# Sheet2.net
KiCad netlist of a schematic drawn in Altium Designer
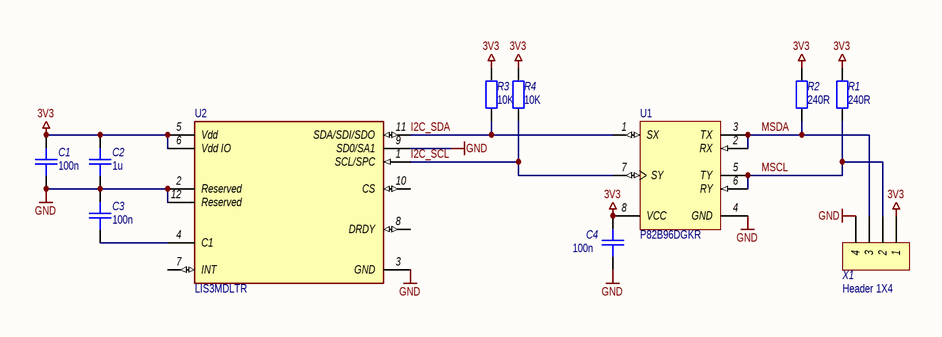
[diagram p0: Sheet2.SchDoc]

(export (version "E")
  (design (tool "Eeschema 10.0.6"))
  (components
    (comp (ref "C1")
      (value "100n")
      (footprint "SMD_C0402")
      (description "Capacitor")
      (fields (field (name "Comment") "K10-79"))
      (libsource (lib "Capacitor") (part "Capacitor"))
    )
    (comp (ref "C2")
      (value "1u")
      (footprint "SMD_C0402")
      (description "Capacitor")
      (fields (field (name "Comment") "K10-79"))
      (libsource (lib "Capacitor") (part "Capacitor"))
    )
    (comp (ref "C3")
      (value "100n")
      (footprint "SMD_C0402")
      (description "Capacitor")
      (fields (field (name "Comment") "K10-79"))
      (libsource (lib "Capacitor") (part "Capacitor"))
    )
    (comp (ref "C4")
      (value "100n")
      (footprint "SMD_C0402")
      (description "Capacitor")
      (fields (field (name "Comment") "K10-79"))
      (libsource (lib "Capacitor") (part "Capacitor"))
    )
    (comp (ref "R1")
      (value "240R")
      (footprint "SMD_0402")
      (description "Resistor")
      (fields (field (name "Comment") "OSM R1-8"))
      (libsource (lib "Resistor") (part "Resistor"))
    )
    (comp (ref "R2")
      (value "240R")
      (footprint "SMD_0402")
      (description "Resistor")
      (fields (field (name "Comment") "OSM R1-8"))
      (libsource (lib "Resistor") (part "Resistor"))
    )
    (comp (ref "R3")
      (value "10K")
      (footprint "SMD_0402")
      (description "Resistor")
      (fields (field (name "Comment") "OSM R1-8"))
      (libsource (lib "") (part "Resistor_1"))
    )
    (comp (ref "R4")
      (value "10K")
      (footprint "SMD_0402")
      (description "Resistor")
      (fields (field (name "Comment") "OSM R1-8"))
      (libsource (lib "Resistor") (part "Resistor"))
    )
    (comp (ref "U1")
      (value "P82B96DGKR")
      (footprint "DGK0008A_M")
      (fields (field (name "MANUFACTURER") "Texas Instruments"))
      (libsource (lib "P82B96DGKR") (part "CMP-0314-00301-2"))
    )
    (comp (ref "U2")
      (value "LIS3MDLTR")
      (footprint "FP-VFLGA-12-8365767-MFG")
      (description "SENSOR MR I2C/SPI 12LGA")
      (fields
        (field (name "OCTOPART") "https://octopart.com/lis3mdltr-stmicroelectronics-29403125")
        (field (name "MANUFACTURER") "STMicroelectronics")
      )
      (libsource (lib "LIS3MDLTR") (part "CMP-2000-07463-2"))
    )
    (comp (ref "X1")
      (value "Header 1X4")
      (footprint "PLS-4")
      (description "Header, 4-Pin, Single row")
      (fields (field (name "НАИМЕНОВАНИЕ") "Header 1X4"))
      (libsource (lib "Connector") (part "Header 1X4"))
    )
  )
  (nets
    (net (code "1") (name "/I2C_SCL") (class "Default")
      (node (ref "R4") (pin "1") (pinfunction "1_1") (pintype "passive"))
      (node (ref "U1") (pin "7") (pinfunction "SY_7") (pintype "bidirectional"))
      (node (ref "U2") (pin "1") (pinfunction "SCL/SPC_1") (pintype "input"))
    )
    (net (code "2") (name "/I2C_SDA") (class "Default")
      (node (ref "R3") (pin "2") (pinfunction "2_2") (pintype "passive"))
      (node (ref "U1") (pin "1") (pinfunction "SX_1") (pintype "bidirectional"))
      (node (ref "U2") (pin "11") (pinfunction "SDA/SDI/SDO_11") (pintype "bidirectional"))
    )
    (net (code "3") (name "/MSCL") (class "Default")
      (node (ref "R1") (pin "1") (pinfunction "1_1") (pintype "passive"))
      (node (ref "U1") (pin "5") (pinfunction "TY_5") (pintype "open_collector"))
      (node (ref "U1") (pin "6") (pinfunction "RY_6") (pintype "input"))
      (node (ref "X1") (pin "2") (pinfunction "2_2") (pintype "passive"))
    )
    (net (code "4") (name "/MSDA") (class "Default")
      (node (ref "R2") (pin "1") (pinfunction "1_1") (pintype "passive"))
      (node (ref "U1") (pin "2") (pinfunction "RX_2") (pintype "input"))
      (node (ref "U1") (pin "3") (pinfunction "TX_3") (pintype "open_collector"))
      (node (ref "X1") (pin "3") (pinfunction "3_3") (pintype "passive"))
    )
    (net (code "5") (name "3V3") (class "Default")
      (node (ref "C1") (pin "2") (pinfunction "2_2") (pintype "passive"))
      (node (ref "C2") (pin "2") (pinfunction "2_2") (pintype "passive"))
      (node (ref "C4") (pin "2") (pinfunction "2_2") (pintype "passive"))
      (node (ref "R1") (pin "2") (pinfunction "2_2") (pintype "passive"))
      (node (ref "R2") (pin "2") (pinfunction "2_2") (pintype "passive"))
      (node (ref "R3") (pin "1") (pinfunction "1_1") (pintype "passive"))
      (node (ref "R4") (pin "2") (pinfunction "2_2") (pintype "passive"))
      (node (ref "U1") (pin "8") (pinfunction "VCC_8") (pintype "power_in"))
      (node (ref "U2") (pin "5") (pinfunction "Vdd_5") (pintype "power_in"))
      (node (ref "U2") (pin "6") (pinfunction "Vdd_IO_6") (pintype "power_in"))
      (node (ref "X1") (pin "1") (pinfunction "1_1") (pintype "passive"))
    )
    (net (code "6") (name "GND") (class "Default")
      (node (ref "C1") (pin "1") (pinfunction "1_1") (pintype "passive"))
      (node (ref "C2") (pin "1") (pinfunction "1_1") (pintype "passive"))
      (node (ref "C3") (pin "2") (pinfunction "2_2") (pintype "passive"))
      (node (ref "C4") (pin "1") (pinfunction "1_1") (pintype "passive"))
      (node (ref "U1") (pin "4") (pinfunction "GND_4") (pintype "power_in"))
      (node (ref "U2") (pin "12") (pinfunction "Reserved_12") (pintype "power_in"))
      (node (ref "U2") (pin "2") (pinfunction "Reserved_2") (pintype "power_in"))
      (node (ref "U2") (pin "3") (pinfunction "GND_3") (pintype "power_in"))
      (node (ref "U2") (pin "9") (pinfunction "SD0/SA1_9") (pintype "passive"))
      (node (ref "X1") (pin "4") (pinfunction "4_4") (pintype "passive"))
    )
    (net (code "7") (name "Net-(U2-C1)") (class "Default")
      (node (ref "C3") (pin "1") (pinfunction "1_1") (pintype "passive"))
      (node (ref "U2") (pin "4") (pinfunction "C1_4") (pintype "passive"))
    )
    (net (code "8") (name "unconnected-(U2-CS-Pad10)") (class "Default")
      (node (ref "U2") (pin "10") (pinfunction "CS_10") (pintype "bidirectional"))
    )
    (net (code "9") (name "unconnected-(U2-DRDY-Pad8)") (class "Default")
      (node (ref "U2") (pin "8") (pinfunction "DRDY_8") (pintype "bidirectional"))
    )
    (net (code "10") (name "unconnected-(U2-INT-Pad7)") (class "Default")
      (node (ref "U2") (pin "7") (pinfunction "INT_7") (pintype "bidirectional"))
    )
  )
)
